# CM_Voltage_Generator.net
KiCad netlist of a schematic drawn in Altium Designer
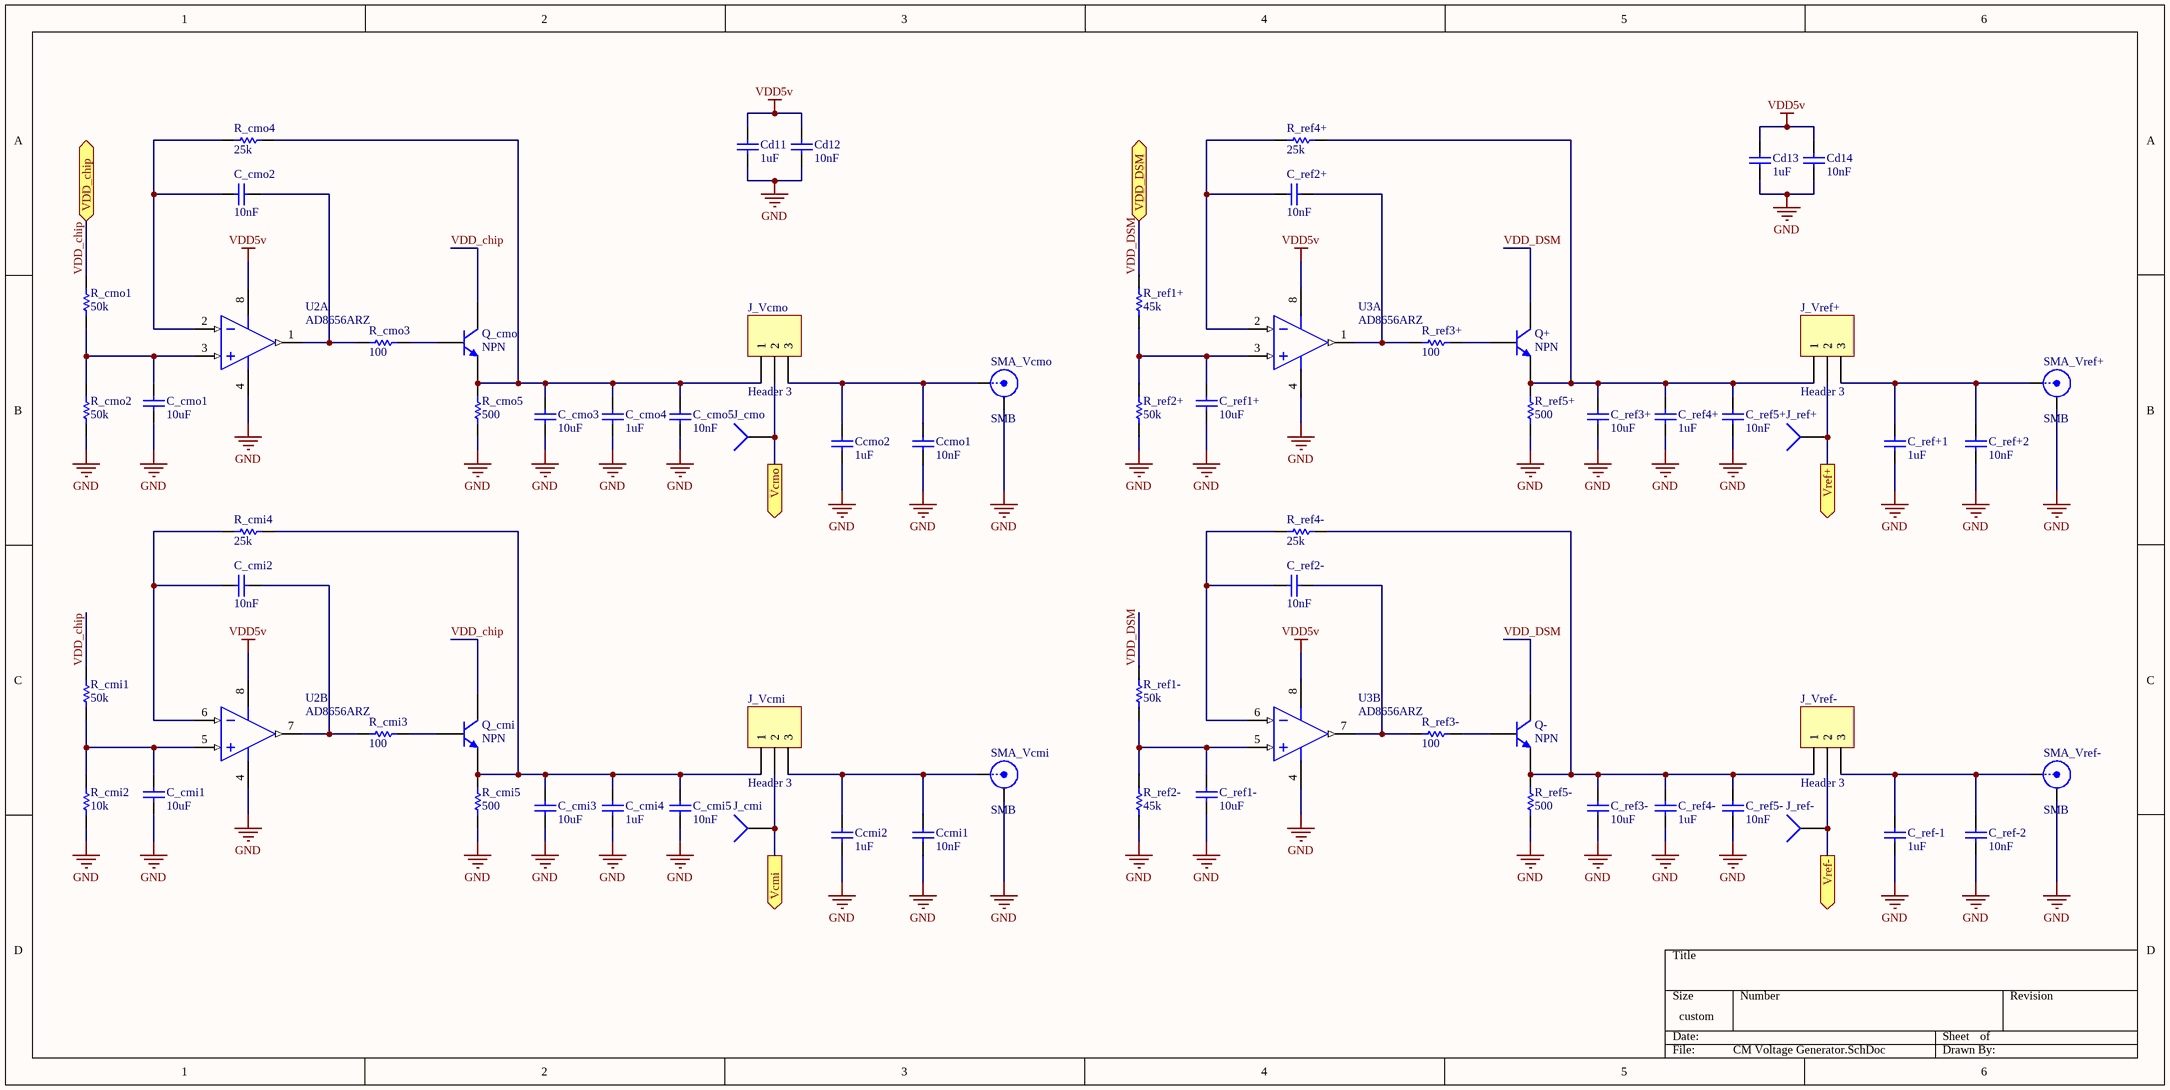
[diagram p0: CM Voltage Generator.SchDoc]

(export (version "E")
  (design (tool "Eeschema 10.0.6"))
  (components
    (comp (ref "Ccmi1")
      (value "10nF")
      (footprint "1608[0603]")
      (description "Capacitor")
      (fields (field (name "Comment") "Cap") (field (name "PUBLISHER") "Altium Limited"))
      (libsource (lib "Miscellaneous Devices") (part "Cap"))
    )
    (comp (ref "Ccmi2")
      (value "1uF")
      (footprint "1608[0603]")
      (description "Capacitor")
      (fields (field (name "Comment") "Cap") (field (name "PUBLISHER") "Altium Limited"))
      (libsource (lib "Miscellaneous Devices") (part "Cap"))
    )
    (comp (ref "Ccmo1")
      (value "10nF")
      (footprint "1608[0603]")
      (description "Capacitor")
      (fields (field (name "Comment") "Cap") (field (name "PUBLISHER") "Altium Limited"))
      (libsource (lib "Miscellaneous Devices") (part "Cap"))
    )
    (comp (ref "Ccmo2")
      (value "1uF")
      (footprint "1608[0603]")
      (description "Capacitor")
      (fields (field (name "Comment") "Cap") (field (name "PUBLISHER") "Altium Limited"))
      (libsource (lib "Miscellaneous Devices") (part "Cap"))
    )
    (comp (ref "Cd11")
      (value "1uF")
      (footprint "1608[0603]")
      (description "Capacitor")
      (fields (field (name "Comment") "Cap") (field (name "PUBLISHER") "Altium Limited"))
      (libsource (lib "Miscellaneous Devices") (part "Cap"))
    )
    (comp (ref "Cd12")
      (value "10nF")
      (footprint "1608[0603]")
      (description "Capacitor")
      (fields (field (name "Comment") "Cap") (field (name "PUBLISHER") "Altium Limited"))
      (libsource (lib "Miscellaneous Devices") (part "Cap"))
    )
    (comp (ref "Cd13")
      (value "1uF")
      (footprint "1608[0603]")
      (description "Capacitor")
      (fields (field (name "Comment") "Cap") (field (name "PUBLISHER") "Altium Limited"))
      (libsource (lib "Miscellaneous Devices") (part "Cap"))
    )
    (comp (ref "Cd14")
      (value "10nF")
      (footprint "1608[0603]")
      (description "Capacitor")
      (fields (field (name "Comment") "Cap") (field (name "PUBLISHER") "Altium Limited"))
      (libsource (lib "Miscellaneous Devices") (part "Cap"))
    )
    (comp (ref "C_cmi1")
      (value "10uF")
      (footprint "1608[0603]")
      (description "Capacitor")
      (fields (field (name "Comment") "Cap") (field (name "PUBLISHER") "Altium Limited"))
      (libsource (lib "Miscellaneous Devices") (part "Cap"))
    )
    (comp (ref "C_cmi2")
      (value "10nF")
      (footprint "1608[0603]")
      (description "Capacitor")
      (fields (field (name "Comment") "Cap") (field (name "PUBLISHER") "Altium Limited"))
      (libsource (lib "Miscellaneous Devices") (part "Cap"))
    )
    (comp (ref "C_cmi3")
      (value "10uF")
      (footprint "1608[0603]")
      (description "Capacitor")
      (fields (field (name "Comment") "Cap") (field (name "PUBLISHER") "Altium Limited"))
      (libsource (lib "Miscellaneous Devices") (part "Cap"))
    )
    (comp (ref "C_cmi4")
      (value "1uF")
      (footprint "1608[0603]")
      (description "Capacitor")
      (fields (field (name "Comment") "Cap") (field (name "PUBLISHER") "Altium Limited"))
      (libsource (lib "Miscellaneous Devices") (part "Cap"))
    )
    (comp (ref "C_cmi5")
      (value "10nF")
      (footprint "1608[0603]")
      (description "Capacitor")
      (fields (field (name "Comment") "Cap") (field (name "PUBLISHER") "Altium Limited"))
      (libsource (lib "Miscellaneous Devices") (part "Cap"))
    )
    (comp (ref "C_cmo1")
      (value "10uF")
      (footprint "1608[0603]")
      (description "Capacitor")
      (fields (field (name "Comment") "Cap") (field (name "PUBLISHER") "Altium Limited"))
      (libsource (lib "Miscellaneous Devices") (part "Cap"))
    )
    (comp (ref "C_cmo2")
      (value "10nF")
      (footprint "1608[0603]")
      (description "Capacitor")
      (fields (field (name "Comment") "Cap") (field (name "PUBLISHER") "Altium Limited"))
      (libsource (lib "Miscellaneous Devices") (part "Cap"))
    )
    (comp (ref "C_cmo3")
      (value "10uF")
      (footprint "1608[0603]")
      (description "Capacitor")
      (fields (field (name "Comment") "Cap") (field (name "PUBLISHER") "Altium Limited"))
      (libsource (lib "Miscellaneous Devices") (part "Cap"))
    )
    (comp (ref "C_cmo4")
      (value "1uF")
      (footprint "1608[0603]")
      (description "Capacitor")
      (fields (field (name "Comment") "Cap") (field (name "PUBLISHER") "Altium Limited"))
      (libsource (lib "Miscellaneous Devices") (part "Cap"))
    )
    (comp (ref "C_cmo5")
      (value "10nF")
      (footprint "1608[0603]")
      (description "Capacitor")
      (fields (field (name "Comment") "Cap") (field (name "PUBLISHER") "Altium Limited"))
      (libsource (lib "Miscellaneous Devices") (part "Cap"))
    )
    (comp (ref "C_ref+1")
      (value "1uF")
      (footprint "1608[0603]")
      (description "Capacitor")
      (fields (field (name "Comment") "Cap") (field (name "PUBLISHER") "Altium Limited"))
      (libsource (lib "Miscellaneous Devices") (part "Cap"))
    )
    (comp (ref "C_ref+2")
      (value "10nF")
      (footprint "1608[0603]")
      (description "Capacitor")
      (fields (field (name "Comment") "Cap") (field (name "PUBLISHER") "Altium Limited"))
      (libsource (lib "Miscellaneous Devices") (part "Cap"))
    )
    (comp (ref "C_ref-1")
      (value "1uF")
      (footprint "1608[0603]")
      (description "Capacitor")
      (fields (field (name "Comment") "Cap") (field (name "PUBLISHER") "Altium Limited"))
      (libsource (lib "Miscellaneous Devices") (part "Cap"))
    )
    (comp (ref "C_ref-2")
      (value "10nF")
      (footprint "1608[0603]")
      (description "Capacitor")
      (fields (field (name "Comment") "Cap") (field (name "PUBLISHER") "Altium Limited"))
      (libsource (lib "Miscellaneous Devices") (part "Cap"))
    )
    (comp (ref "C_ref1+")
      (value "10uF")
      (footprint "1608[0603]")
      (description "Capacitor")
      (fields (field (name "Comment") "Cap") (field (name "PUBLISHER") "Altium Limited"))
      (libsource (lib "Miscellaneous Devices") (part "Cap"))
    )
    (comp (ref "C_ref1-")
      (value "10uF")
      (footprint "1608[0603]")
      (description "Capacitor")
      (fields (field (name "Comment") "Cap") (field (name "PUBLISHER") "Altium Limited"))
      (libsource (lib "Miscellaneous Devices") (part "Cap"))
    )
    (comp (ref "C_ref2+")
      (value "10nF")
      (footprint "1608[0603]")
      (description "Capacitor")
      (fields (field (name "Comment") "Cap") (field (name "PUBLISHER") "Altium Limited"))
      (libsource (lib "Miscellaneous Devices") (part "Cap"))
    )
    (comp (ref "C_ref2-")
      (value "10nF")
      (footprint "1608[0603]")
      (description "Capacitor")
      (fields (field (name "Comment") "Cap") (field (name "PUBLISHER") "Altium Limited"))
      (libsource (lib "Miscellaneous Devices") (part "Cap"))
    )
    (comp (ref "C_ref3+")
      (value "10uF")
      (footprint "1608[0603]")
      (description "Capacitor")
      (fields (field (name "Comment") "Cap") (field (name "PUBLISHER") "Altium Limited"))
      (libsource (lib "Miscellaneous Devices") (part "Cap"))
    )
    (comp (ref "C_ref3-")
      (value "10uF")
      (footprint "1608[0603]")
      (description "Capacitor")
      (fields (field (name "Comment") "Cap") (field (name "PUBLISHER") "Altium Limited"))
      (libsource (lib "Miscellaneous Devices") (part "Cap"))
    )
    (comp (ref "C_ref4+")
      (value "1uF")
      (footprint "1608[0603]")
      (description "Capacitor")
      (fields (field (name "Comment") "Cap") (field (name "PUBLISHER") "Altium Limited"))
      (libsource (lib "Miscellaneous Devices") (part "Cap"))
    )
    (comp (ref "C_ref4-")
      (value "1uF")
      (footprint "1608[0603]")
      (description "Capacitor")
      (fields (field (name "Comment") "Cap") (field (name "PUBLISHER") "Altium Limited"))
      (libsource (lib "Miscellaneous Devices") (part "Cap"))
    )
    (comp (ref "C_ref5+")
      (value "10nF")
      (footprint "1608[0603]")
      (description "Capacitor")
      (fields (field (name "Comment") "Cap") (field (name "PUBLISHER") "Altium Limited"))
      (libsource (lib "Miscellaneous Devices") (part "Cap"))
    )
    (comp (ref "C_ref5-")
      (value "10nF")
      (footprint "1608[0603]")
      (description "Capacitor")
      (fields (field (name "Comment") "Cap") (field (name "PUBLISHER") "Altium Limited"))
      (libsource (lib "Miscellaneous Devices") (part "Cap"))
    )
    (comp (ref "J_cmi")
      (value "Socket")
      (footprint "PIN1")
      (fields (field (name "PUBLISHER") "Altium Limited"))
      (libsource (lib "Miscellaneous Connectors") (part "Socket"))
    )
    (comp (ref "J_cmo")
      (value "Socket")
      (footprint "PIN1")
      (fields (field (name "PUBLISHER") "Altium Limited"))
      (libsource (lib "Miscellaneous Connectors") (part "Socket"))
    )
    (comp (ref "J_ref+")
      (value "Socket")
      (footprint "PIN1")
      (fields (field (name "PUBLISHER") "Altium Limited"))
      (libsource (lib "Miscellaneous Connectors") (part "Socket"))
    )
    (comp (ref "J_ref-")
      (value "Socket")
      (footprint "PIN1")
      (fields (field (name "PUBLISHER") "Altium Limited"))
      (libsource (lib "Miscellaneous Connectors") (part "Socket"))
    )
    (comp (ref "J_Vcmi")
      (value "Header 3")
      (footprint "HDR1X3")
      (description "Header, 3-Pin")
      (fields (field (name "PUBLISHER") "Altium Limited"))
      (libsource (lib "Miscellaneous Connectors") (part "Header 3"))
    )
    (comp (ref "J_Vcmo")
      (value "Header 3")
      (footprint "HDR1X3")
      (description "Header, 3-Pin")
      (fields (field (name "PUBLISHER") "Altium Limited"))
      (libsource (lib "Miscellaneous Connectors") (part "Header 3"))
    )
    (comp (ref "J_Vref+")
      (value "Header 3")
      (footprint "HDR1X3")
      (description "Header, 3-Pin")
      (fields (field (name "PUBLISHER") "Altium Limited"))
      (libsource (lib "Miscellaneous Connectors") (part "Header 3"))
    )
    (comp (ref "J_Vref-")
      (value "Header 3")
      (footprint "HDR1X3")
      (description "Header, 3-Pin")
      (fields (field (name "PUBLISHER") "Altium Limited"))
      (libsource (lib "Miscellaneous Connectors") (part "Header 3"))
    )
    (comp (ref "Q+")
      (value "NPN")
      (footprint "SOT-23_M")
      (description "NPN Bipolar Transistor")
      (fields (field (name "PUBLISHER") "Altium Limited"))
      (libsource (lib "Miscellaneous Devices") (part "NPN"))
    )
    (comp (ref "Q-")
      (value "NPN")
      (footprint "SOT-23_M")
      (description "NPN Bipolar Transistor")
      (fields (field (name "PUBLISHER") "Altium Limited"))
      (libsource (lib "Miscellaneous Devices") (part "NPN"))
    )
    (comp (ref "Q_cmi")
      (value "NPN")
      (footprint "SOT-23_M")
      (description "NPN Bipolar Transistor")
      (fields (field (name "PUBLISHER") "Altium Limited"))
      (libsource (lib "Miscellaneous Devices") (part "NPN"))
    )
    (comp (ref "Q_cmo")
      (value "NPN")
      (footprint "SOT-23_M")
      (description "NPN Bipolar Transistor")
      (fields (field (name "PUBLISHER") "Altium Limited"))
      (libsource (lib "Miscellaneous Devices") (part "NPN"))
    )
    (comp (ref "R_cmi1")
      (value "50k")
      (footprint "1608[0603]")
      (description "Resistor")
      (fields (field (name "Comment") "Res1") (field (name "PUBLISHER") "Altium Limited"))
      (libsource (lib "Miscellaneous Devices") (part "Res1"))
    )
    (comp (ref "R_cmi2")
      (value "10k")
      (footprint "1608[0603]")
      (description "Resistor")
      (fields (field (name "Comment") "Res1") (field (name "PUBLISHER") "Altium Limited"))
      (libsource (lib "Miscellaneous Devices") (part "Res1"))
    )
    (comp (ref "R_cmi3")
      (value "100")
      (footprint "1608[0603]")
      (description "Resistor")
      (fields (field (name "Comment") "Res1") (field (name "PUBLISHER") "Altium Limited"))
      (libsource (lib "Miscellaneous Devices") (part "Res1"))
    )
    (comp (ref "R_cmi4")
      (value "25k")
      (footprint "1608[0603]")
      (description "Resistor")
      (fields (field (name "Comment") "Res1") (field (name "PUBLISHER") "Altium Limited"))
      (libsource (lib "Miscellaneous Devices") (part "Res1"))
    )
    (comp (ref "R_cmi5")
      (value "500")
      (footprint "1608[0603]")
      (description "Resistor")
      (fields (field (name "Comment") "Res1") (field (name "PUBLISHER") "Altium Limited"))
      (libsource (lib "Miscellaneous Devices") (part "Res1"))
    )
    (comp (ref "R_cmo1")
      (value "50k")
      (footprint "1608[0603]")
      (description "Resistor")
      (fields (field (name "Comment") "Res1") (field (name "PUBLISHER") "Altium Limited"))
      (libsource (lib "Miscellaneous Devices") (part "Res1"))
    )
    (comp (ref "R_cmo2")
      (value "50k")
      (footprint "1608[0603]")
      (description "Resistor")
      (fields (field (name "Comment") "Res1") (field (name "PUBLISHER") "Altium Limited"))
      (libsource (lib "Miscellaneous Devices") (part "Res1"))
    )
    (comp (ref "R_cmo3")
      (value "100")
      (footprint "1608[0603]")
      (description "Resistor")
      (fields (field (name "Comment") "Res1") (field (name "PUBLISHER") "Altium Limited"))
      (libsource (lib "Miscellaneous Devices") (part "Res1"))
    )
    (comp (ref "R_cmo4")
      (value "25k")
      (footprint "1608[0603]")
      (description "Resistor")
      (fields (field (name "Comment") "Res1") (field (name "PUBLISHER") "Altium Limited"))
      (libsource (lib "Miscellaneous Devices") (part "Res1"))
    )
    (comp (ref "R_cmo5")
      (value "500")
      (footprint "1608[0603]")
      (description "Resistor")
      (fields (field (name "Comment") "Res1") (field (name "PUBLISHER") "Altium Limited"))
      (libsource (lib "Miscellaneous Devices") (part "Res1"))
    )
    (comp (ref "R_ref1+")
      (value "45k")
      (footprint "1608[0603]")
      (description "Resistor")
      (fields (field (name "Comment") "Res1") (field (name "PUBLISHER") "Altium Limited"))
      (libsource (lib "Miscellaneous Devices") (part "Res1"))
    )
    (comp (ref "R_ref1-")
      (value "50k")
      (footprint "1608[0603]")
      (description "Resistor")
      (fields (field (name "Comment") "Res1") (field (name "PUBLISHER") "Altium Limited"))
      (libsource (lib "Miscellaneous Devices") (part "Res1"))
    )
    (comp (ref "R_ref2+")
      (value "50k")
      (footprint "1608[0603]")
      (description "Resistor")
      (fields (field (name "Comment") "Res1") (field (name "PUBLISHER") "Altium Limited"))
      (libsource (lib "Miscellaneous Devices") (part "Res1"))
    )
    (comp (ref "R_ref2-")
      (value "45k")
      (footprint "1608[0603]")
      (description "Resistor")
      (fields (field (name "Comment") "Res1") (field (name "PUBLISHER") "Altium Limited"))
      (libsource (lib "Miscellaneous Devices") (part "Res1"))
    )
    (comp (ref "R_ref3+")
      (value "100")
      (footprint "1608[0603]")
      (description "Resistor")
      (fields (field (name "Comment") "Res1") (field (name "PUBLISHER") "Altium Limited"))
      (libsource (lib "Miscellaneous Devices") (part "Res1"))
    )
    (comp (ref "R_ref3-")
      (value "100")
      (footprint "1608[0603]")
      (description "Resistor")
      (fields (field (name "Comment") "Res1") (field (name "PUBLISHER") "Altium Limited"))
      (libsource (lib "Miscellaneous Devices") (part "Res1"))
    )
    (comp (ref "R_ref4+")
      (value "25k")
      (footprint "1608[0603]")
      (description "Resistor")
      (fields (field (name "Comment") "Res1") (field (name "PUBLISHER") "Altium Limited"))
      (libsource (lib "Miscellaneous Devices") (part "Res1"))
    )
    (comp (ref "R_ref4-")
      (value "25k")
      (footprint "1608[0603]")
      (description "Resistor")
      (fields (field (name "Comment") "Res1") (field (name "PUBLISHER") "Altium Limited"))
      (libsource (lib "Miscellaneous Devices") (part "Res1"))
    )
    (comp (ref "R_ref5+")
      (value "500")
      (footprint "1608[0603]")
      (description "Resistor")
      (fields (field (name "Comment") "Res1") (field (name "PUBLISHER") "Altium Limited"))
      (libsource (lib "Miscellaneous Devices") (part "Res1"))
    )
    (comp (ref "R_ref5-")
      (value "500")
      (footprint "1608[0603]")
      (description "Resistor")
      (fields (field (name "Comment") "Res1") (field (name "PUBLISHER") "Altium Limited"))
      (libsource (lib "Miscellaneous Devices") (part "Res1"))
    )
    (comp (ref "SMA_Vcmi")
      (value "SMB")
      (footprint "SMB_V-RJ45")
      (description "SMB Straight Connector")
      (fields (field (name "PUBLISHER") "Altium Limited"))
      (libsource (lib "Miscellaneous Connectors") (part "SMB"))
    )
    (comp (ref "SMA_Vcmo")
      (value "SMB")
      (footprint "SMB_V-RJ45")
      (description "SMB Straight Connector")
      (fields (field (name "PUBLISHER") "Altium Limited"))
      (libsource (lib "Miscellaneous Connectors") (part "SMB"))
    )
    (comp (ref "SMA_Vref+")
      (value "SMB")
      (footprint "SMB_V-RJ45")
      (description "SMB Straight Connector")
      (fields (field (name "PUBLISHER") "Altium Limited"))
      (libsource (lib "Miscellaneous Connectors") (part "SMB"))
    )
    (comp (ref "SMA_Vref-")
      (value "SMB")
      (footprint "SMB_V-RJ45")
      (description "SMB Straight Connector")
      (fields (field (name "PUBLISHER") "Altium Limited"))
      (libsource (lib "Miscellaneous Connectors") (part "SMB"))
    )
    (comp (ref "U2")
      (value "AD8656ARZ")
      (footprint "ADI-R-8_N")
      (fields (field (name "GENERIC PART NUMBER") "AD8656") (field (name "MANUFACTURER") "Analog Devices"))
      (libsource (lib "Analog Devices Operational Amplifiers") (part "AD8656ARZ"))
    )
    (comp (ref "U3")
      (value "AD8656ARZ")
      (footprint "ADI-R-8_N")
      (fields (field (name "GENERIC PART NUMBER") "AD8656") (field (name "MANUFACTURER") "Analog Devices"))
      (libsource (lib "Analog Devices Operational Amplifiers") (part "AD8656ARZ"))
    )
  )
  (nets
    (net (code "1") (name "/VDD_DSM") (class "Default")
      (node (ref "Q+") (pin "1") (pinfunction "C_1") (pintype "passive"))
      (node (ref "Q-") (pin "1") (pinfunction "C_1") (pintype "passive"))
      (node (ref "R_ref1+") (pin "2") (pinfunction "2_2") (pintype "passive"))
      (node (ref "R_ref1-") (pin "2") (pinfunction "2_2") (pintype "passive"))
    )
    (net (code "2") (name "/VDD_chip") (class "Default")
      (node (ref "Q_cmi") (pin "1") (pinfunction "C_1") (pintype "passive"))
      (node (ref "Q_cmo") (pin "1") (pinfunction "C_1") (pintype "passive"))
      (node (ref "R_cmi1") (pin "2") (pinfunction "2_2") (pintype "passive"))
      (node (ref "R_cmo1") (pin "2") (pinfunction "2_2") (pintype "passive"))
    )
    (net (code "3") (name "/Vcmi") (class "Default")
      (node (ref "J_Vcmi") (pin "2") (pinfunction "2_2") (pintype "passive"))
      (node (ref "J_cmi") (pin "1") (pinfunction "1_1") (pintype "passive"))
    )
    (net (code "4") (name "/Vcmo") (class "Default")
      (node (ref "J_Vcmo") (pin "2") (pinfunction "2_2") (pintype "passive"))
      (node (ref "J_cmo") (pin "1") (pinfunction "1_1") (pintype "passive"))
    )
    (net (code "5") (name "/Vref+") (class "Default")
      (node (ref "J_Vref+") (pin "2") (pinfunction "2_2") (pintype "passive"))
      (node (ref "J_ref+") (pin "1") (pinfunction "1_1") (pintype "passive"))
    )
    (net (code "6") (name "/Vref-") (class "Default")
      (node (ref "J_Vref-") (pin "2") (pinfunction "2_2") (pintype "passive"))
      (node (ref "J_ref-") (pin "1") (pinfunction "1_1") (pintype "passive"))
    )
    (net (code "7") (name "GND") (class "Default")
      (node (ref "C_cmi1") (pin "2") (pinfunction "2_2") (pintype "passive"))
      (node (ref "C_cmi3") (pin "2") (pinfunction "2_2") (pintype "passive"))
      (node (ref "C_cmi4") (pin "2") (pinfunction "2_2") (pintype "passive"))
      (node (ref "C_cmi5") (pin "2") (pinfunction "2_2") (pintype "passive"))
      (node (ref "C_cmo1") (pin "2") (pinfunction "2_2") (pintype "passive"))
      (node (ref "C_cmo3") (pin "2") (pinfunction "2_2") (pintype "passive"))
      (node (ref "C_cmo4") (pin "2") (pinfunction "2_2") (pintype "passive"))
      (node (ref "C_cmo5") (pin "2") (pinfunction "2_2") (pintype "passive"))
      (node (ref "C_ref+1") (pin "2") (pinfunction "2_2") (pintype "passive"))
      (node (ref "C_ref+2") (pin "2") (pinfunction "2_2") (pintype "passive"))
      (node (ref "C_ref-1") (pin "2") (pinfunction "2_2") (pintype "passive"))
      (node (ref "C_ref-2") (pin "2") (pinfunction "2_2") (pintype "passive"))
      (node (ref "C_ref1+") (pin "2") (pinfunction "2_2") (pintype "passive"))
      (node (ref "C_ref1-") (pin "2") (pinfunction "2_2") (pintype "passive"))
      (node (ref "C_ref3+") (pin "2") (pinfunction "2_2") (pintype "passive"))
      (node (ref "C_ref3-") (pin "2") (pinfunction "2_2") (pintype "passive"))
      (node (ref "C_ref4+") (pin "2") (pinfunction "2_2") (pintype "passive"))
      (node (ref "C_ref4-") (pin "2") (pinfunction "2_2") (pintype "passive"))
      (node (ref "C_ref5+") (pin "2") (pinfunction "2_2") (pintype "passive"))
      (node (ref "C_ref5-") (pin "2") (pinfunction "2_2") (pintype "passive"))
      (node (ref "Ccmi1") (pin "2") (pinfunction "2_2") (pintype "passive"))
      (node (ref "Ccmi2") (pin "2") (pinfunction "2_2") (pintype "passive"))
      (node (ref "Ccmo1") (pin "2") (pinfunction "2_2") (pintype "passive"))
      (node (ref "Ccmo2") (pin "2") (pinfunction "2_2") (pintype "passive"))
      (node (ref "Cd11") (pin "2") (pinfunction "2_2") (pintype "passive"))
      (node (ref "Cd12") (pin "2") (pinfunction "2_2") (pintype "passive"))
      (node (ref "Cd13") (pin "2") (pinfunction "2_2") (pintype "passive"))
      (node (ref "Cd14") (pin "2") (pinfunction "2_2") (pintype "passive"))
      (node (ref "R_cmi2") (pin "1") (pinfunction "1_1") (pintype "passive"))
      (node (ref "R_cmi5") (pin "2") (pinfunction "2_2") (pintype "passive"))
      (node (ref "R_cmo2") (pin "1") (pinfunction "1_1") (pintype "passive"))
      (node (ref "R_cmo5") (pin "2") (pinfunction "2_2") (pintype "passive"))
      (node (ref "R_ref2+") (pin "1") (pinfunction "1_1") (pintype "passive"))
      (node (ref "R_ref2-") (pin "1") (pinfunction "1_1") (pintype "passive"))
      (node (ref "R_ref5+") (pin "2") (pinfunction "2_2") (pintype "passive"))
      (node (ref "R_ref5-") (pin "2") (pinfunction "2_2") (pintype "passive"))
      (node (ref "SMA_Vcmi") (pin "2") (pinfunction "Y_2") (pintype "passive"))
      (node (ref "SMA_Vcmo") (pin "2") (pinfunction "Y_2") (pintype "passive"))
      (node (ref "SMA_Vref+") (pin "2") (pinfunction "Y_2") (pintype "passive"))
      (node (ref "SMA_Vref-") (pin "2") (pinfunction "Y_2") (pintype "passive"))
      (node (ref "U2") (pin "4") (pinfunction "-V_4") (pintype "power_in"))
      (node (ref "U3") (pin "4") (pinfunction "-V_4") (pintype "power_in"))
    )
    (net (code "8") (name "Net-(Q+-B)") (class "Default")
      (node (ref "Q+") (pin "2") (pinfunction "B_2") (pintype "passive"))
      (node (ref "R_ref3+") (pin "1") (pinfunction "1_1") (pintype "passive"))
    )
    (net (code "9") (name "Net-(Q+-E)") (class "Default")
      (node (ref "C_ref3+") (pin "1") (pinfunction "1_1") (pintype "passive"))
      (node (ref "C_ref4+") (pin "1") (pinfunction "1_1") (pintype "passive"))
      (node (ref "C_ref5+") (pin "1") (pinfunction "1_1") (pintype "passive"))
      (node (ref "J_Vref+") (pin "1") (pinfunction "1_1") (pintype "passive"))
      (node (ref "Q+") (pin "3") (pinfunction "E_3") (pintype "passive"))
      (node (ref "R_ref4+") (pin "1") (pinfunction "1_1") (pintype "passive"))
      (node (ref "R_ref5+") (pin "1") (pinfunction "1_1") (pintype "passive"))
    )
    (net (code "10") (name "Net-(Q--B)") (class "Default")
      (node (ref "Q-") (pin "2") (pinfunction "B_2") (pintype "passive"))
      (node (ref "R_ref3-") (pin "1") (pinfunction "1_1") (pintype "passive"))
    )
    (net (code "11") (name "Net-(Q--E)") (class "Default")
      (node (ref "C_ref3-") (pin "1") (pinfunction "1_1") (pintype "passive"))
      (node (ref "C_ref4-") (pin "1") (pinfunction "1_1") (pintype "passive"))
      (node (ref "C_ref5-") (pin "1") (pinfunction "1_1") (pintype "passive"))
      (node (ref "J_Vref-") (pin "1") (pinfunction "1_1") (pintype "passive"))
      (node (ref "Q-") (pin "3") (pinfunction "E_3") (pintype "passive"))
      (node (ref "R_ref4-") (pin "1") (pinfunction "1_1") (pintype "passive"))
      (node (ref "R_ref5-") (pin "1") (pinfunction "1_1") (pintype "passive"))
    )
    (net (code "12") (name "Net-(Q_cmi-B)") (class "Default")
      (node (ref "Q_cmi") (pin "2") (pinfunction "B_2") (pintype "passive"))
      (node (ref "R_cmi3") (pin "1") (pinfunction "1_1") (pintype "passive"))
    )
    (net (code "13") (name "Net-(Q_cmi-E)") (class "Default")
      (node (ref "C_cmi3") (pin "1") (pinfunction "1_1") (pintype "passive"))
      (node (ref "C_cmi4") (pin "1") (pinfunction "1_1") (pintype "passive"))
      (node (ref "C_cmi5") (pin "1") (pinfunction "1_1") (pintype "passive"))
      (node (ref "J_Vcmi") (pin "1") (pinfunction "1_1") (pintype "passive"))
      (node (ref "Q_cmi") (pin "3") (pinfunction "E_3") (pintype "passive"))
      (node (ref "R_cmi4") (pin "1") (pinfunction "1_1") (pintype "passive"))
      (node (ref "R_cmi5") (pin "1") (pinfunction "1_1") (pintype "passive"))
    )
    (net (code "14") (name "Net-(Q_cmo-B)") (class "Default")
      (node (ref "Q_cmo") (pin "2") (pinfunction "B_2") (pintype "passive"))
      (node (ref "R_cmo3") (pin "1") (pinfunction "1_1") (pintype "passive"))
    )
    (net (code "15") (name "Net-(Q_cmo-E)") (class "Default")
      (node (ref "C_cmo3") (pin "1") (pinfunction "1_1") (pintype "passive"))
      (node (ref "C_cmo4") (pin "1") (pinfunction "1_1") (pintype "passive"))
      (node (ref "C_cmo5") (pin "1") (pinfunction "1_1") (pintype "passive"))
      (node (ref "J_Vcmo") (pin "1") (pinfunction "1_1") (pintype "passive"))
      (node (ref "Q_cmo") (pin "3") (pinfunction "E_3") (pintype "passive"))
      (node (ref "R_cmo4") (pin "1") (pinfunction "1_1") (pintype "passive"))
      (node (ref "R_cmo5") (pin "1") (pinfunction "1_1") (pintype "passive"))
    )
    (net (code "16") (name "Net-(SMA_Vcmi-X)") (class "Default")
      (node (ref "Ccmi1") (pin "1") (pinfunction "1_1") (pintype "passive"))
      (node (ref "Ccmi2") (pin "1") (pinfunction "1_1") (pintype "passive"))
      (node (ref "J_Vcmi") (pin "3") (pinfunction "3_3") (pintype "passive"))
      (node (ref "SMA_Vcmi") (pin "1") (pinfunction "X_1") (pintype "passive"))
    )
    (net (code "17") (name "Net-(SMA_Vcmo-X)") (class "Default")
      (node (ref "Ccmo1") (pin "1") (pinfunction "1_1") (pintype "passive"))
      (node (ref "Ccmo2") (pin "1") (pinfunction "1_1") (pintype "passive"))
      (node (ref "J_Vcmo") (pin "3") (pinfunction "3_3") (pintype "passive"))
      (node (ref "SMA_Vcmo") (pin "1") (pinfunction "X_1") (pintype "passive"))
    )
    (net (code "18") (name "Net-(SMA_Vref+-X)") (class "Default")
      (node (ref "C_ref+1") (pin "1") (pinfunction "1_1") (pintype "passive"))
      (node (ref "C_ref+2") (pin "1") (pinfunction "1_1") (pintype "passive"))
      (node (ref "J_Vref+") (pin "3") (pinfunction "3_3") (pintype "passive"))
      (node (ref "SMA_Vref+") (pin "1") (pinfunction "X_1") (pintype "passive"))
    )
    (net (code "19") (name "Net-(SMA_Vref--X)") (class "Default")
      (node (ref "C_ref-1") (pin "1") (pinfunction "1_1") (pintype "passive"))
      (node (ref "C_ref-2") (pin "1") (pinfunction "1_1") (pintype "passive"))
      (node (ref "J_Vref-") (pin "3") (pinfunction "3_3") (pintype "passive"))
      (node (ref "SMA_Vref-") (pin "1") (pinfunction "X_1") (pintype "passive"))
    )
    (net (code "20") (name "Net-(U2A-+IN_A)") (class "Default")
      (node (ref "C_cmo1") (pin "1") (pinfunction "1_1") (pintype "passive"))
      (node (ref "R_cmo1") (pin "1") (pinfunction "1_1") (pintype "passive"))
      (node (ref "R_cmo2") (pin "2") (pinfunction "2_2") (pintype "passive"))
      (node (ref "U2") (pin "3") (pinfunction "+IN_A_3") (pintype "input"))
    )
    (net (code "21") (name "Net-(U2A--IN_A)") (class "Default")
      (node (ref "C_cmo2") (pin "1") (pinfunction "1_1") (pintype "passive"))
      (node (ref "R_cmo4") (pin "2") (pinfunction "2_2") (pintype "passive"))
      (node (ref "U2") (pin "2") (pinfunction "-IN_A_2") (pintype "input"))
    )
    (net (code "22") (name "Net-(U2A-OUT_A)") (class "Default")
      (node (ref "C_cmo2") (pin "2") (pinfunction "2_2") (pintype "passive"))
      (node (ref "R_cmo3") (pin "2") (pinfunction "2_2") (pintype "passive"))
      (node (ref "U2") (pin "1") (pinfunction "OUT_A_1") (pintype "output"))
    )
    (net (code "23") (name "Net-(U2B-+IN_B)") (class "Default")
      (node (ref "C_cmi1") (pin "1") (pinfunction "1_1") (pintype "passive"))
      (node (ref "R_cmi1") (pin "1") (pinfunction "1_1") (pintype "passive"))
      (node (ref "R_cmi2") (pin "2") (pinfunction "2_2") (pintype "passive"))
      (node (ref "U2") (pin "5") (pinfunction "+IN_B_5") (pintype "input"))
    )
    (net (code "24") (name "Net-(U2B--IN_B)") (class "Default")
      (node (ref "C_cmi2") (pin "1") (pinfunction "1_1") (pintype "passive"))
      (node (ref "R_cmi4") (pin "2") (pinfunction "2_2") (pintype "passive"))
      (node (ref "U2") (pin "6") (pinfunction "-IN_B_6") (pintype "input"))
    )
    (net (code "25") (name "Net-(U2B-OUT_B)") (class "Default")
      (node (ref "C_cmi2") (pin "2") (pinfunction "2_2") (pintype "passive"))
      (node (ref "R_cmi3") (pin "2") (pinfunction "2_2") (pintype "passive"))
      (node (ref "U2") (pin "7") (pinfunction "OUT_B_7") (pintype "output"))
    )
    (net (code "26") (name "Net-(U3A-+IN_A)") (class "Default")
      (node (ref "C_ref1+") (pin "1") (pinfunction "1_1") (pintype "passive"))
      (node (ref "R_ref1+") (pin "1") (pinfunction "1_1") (pintype "passive"))
      (node (ref "R_ref2+") (pin "2") (pinfunction "2_2") (pintype "passive"))
      (node (ref "U3") (pin "3") (pinfunction "+IN_A_3") (pintype "input"))
    )
    (net (code "27") (name "Net-(U3A--IN_A)") (class "Default")
      (node (ref "C_ref2+") (pin "1") (pinfunction "1_1") (pintype "passive"))
      (node (ref "R_ref4+") (pin "2") (pinfunction "2_2") (pintype "passive"))
      (node (ref "U3") (pin "2") (pinfunction "-IN_A_2") (pintype "input"))
    )
    (net (code "28") (name "Net-(U3A-OUT_A)") (class "Default")
      (node (ref "C_ref2+") (pin "2") (pinfunction "2_2") (pintype "passive"))
      (node (ref "R_ref3+") (pin "2") (pinfunction "2_2") (pintype "passive"))
      (node (ref "U3") (pin "1") (pinfunction "OUT_A_1") (pintype "output"))
    )
    (net (code "29") (name "Net-(U3B-+IN_B)") (class "Default")
      (node (ref "C_ref1-") (pin "1") (pinfunction "1_1") (pintype "passive"))
      (node (ref "R_ref1-") (pin "1") (pinfunction "1_1") (pintype "passive"))
      (node (ref "R_ref2-") (pin "2") (pinfunction "2_2") (pintype "passive"))
      (node (ref "U3") (pin "5") (pinfunction "+IN_B_5") (pintype "input"))
    )
    (net (code "30") (name "Net-(U3B--IN_B)") (class "Default")
      (node (ref "C_ref2-") (pin "1") (pinfunction "1_1") (pintype "passive"))
      (node (ref "R_ref4-") (pin "2") (pinfunction "2_2") (pintype "passive"))
      (node (ref "U3") (pin "6") (pinfunction "-IN_B_6") (pintype "input"))
    )
    (net (code "31") (name "Net-(U3B-OUT_B)") (class "Default")
      (node (ref "C_ref2-") (pin "2") (pinfunction "2_2") (pintype "passive"))
      (node (ref "R_ref3-") (pin "2") (pinfunction "2_2") (pintype "passive"))
      (node (ref "U3") (pin "7") (pinfunction "OUT_B_7") (pintype "output"))
    )
    (net (code "32") (name "VDD5v") (class "Default")
      (node (ref "Cd11") (pin "1") (pinfunction "1_1") (pintype "passive"))
      (node (ref "Cd12") (pin "1") (pinfunction "1_1") (pintype "passive"))
      (node (ref "Cd13") (pin "1") (pinfunction "1_1") (pintype "passive"))
      (node (ref "Cd14") (pin "1") (pinfunction "1_1") (pintype "passive"))
      (node (ref "U2") (pin "8") (pinfunction "+V_8") (pintype "power_in"))
      (node (ref "U3") (pin "8") (pinfunction "+V_8") (pintype "power_in"))
    )
  )
)
